# Codeshelf-0007_v03.net
KiCad netlist of a schematic drawn in EAGLE
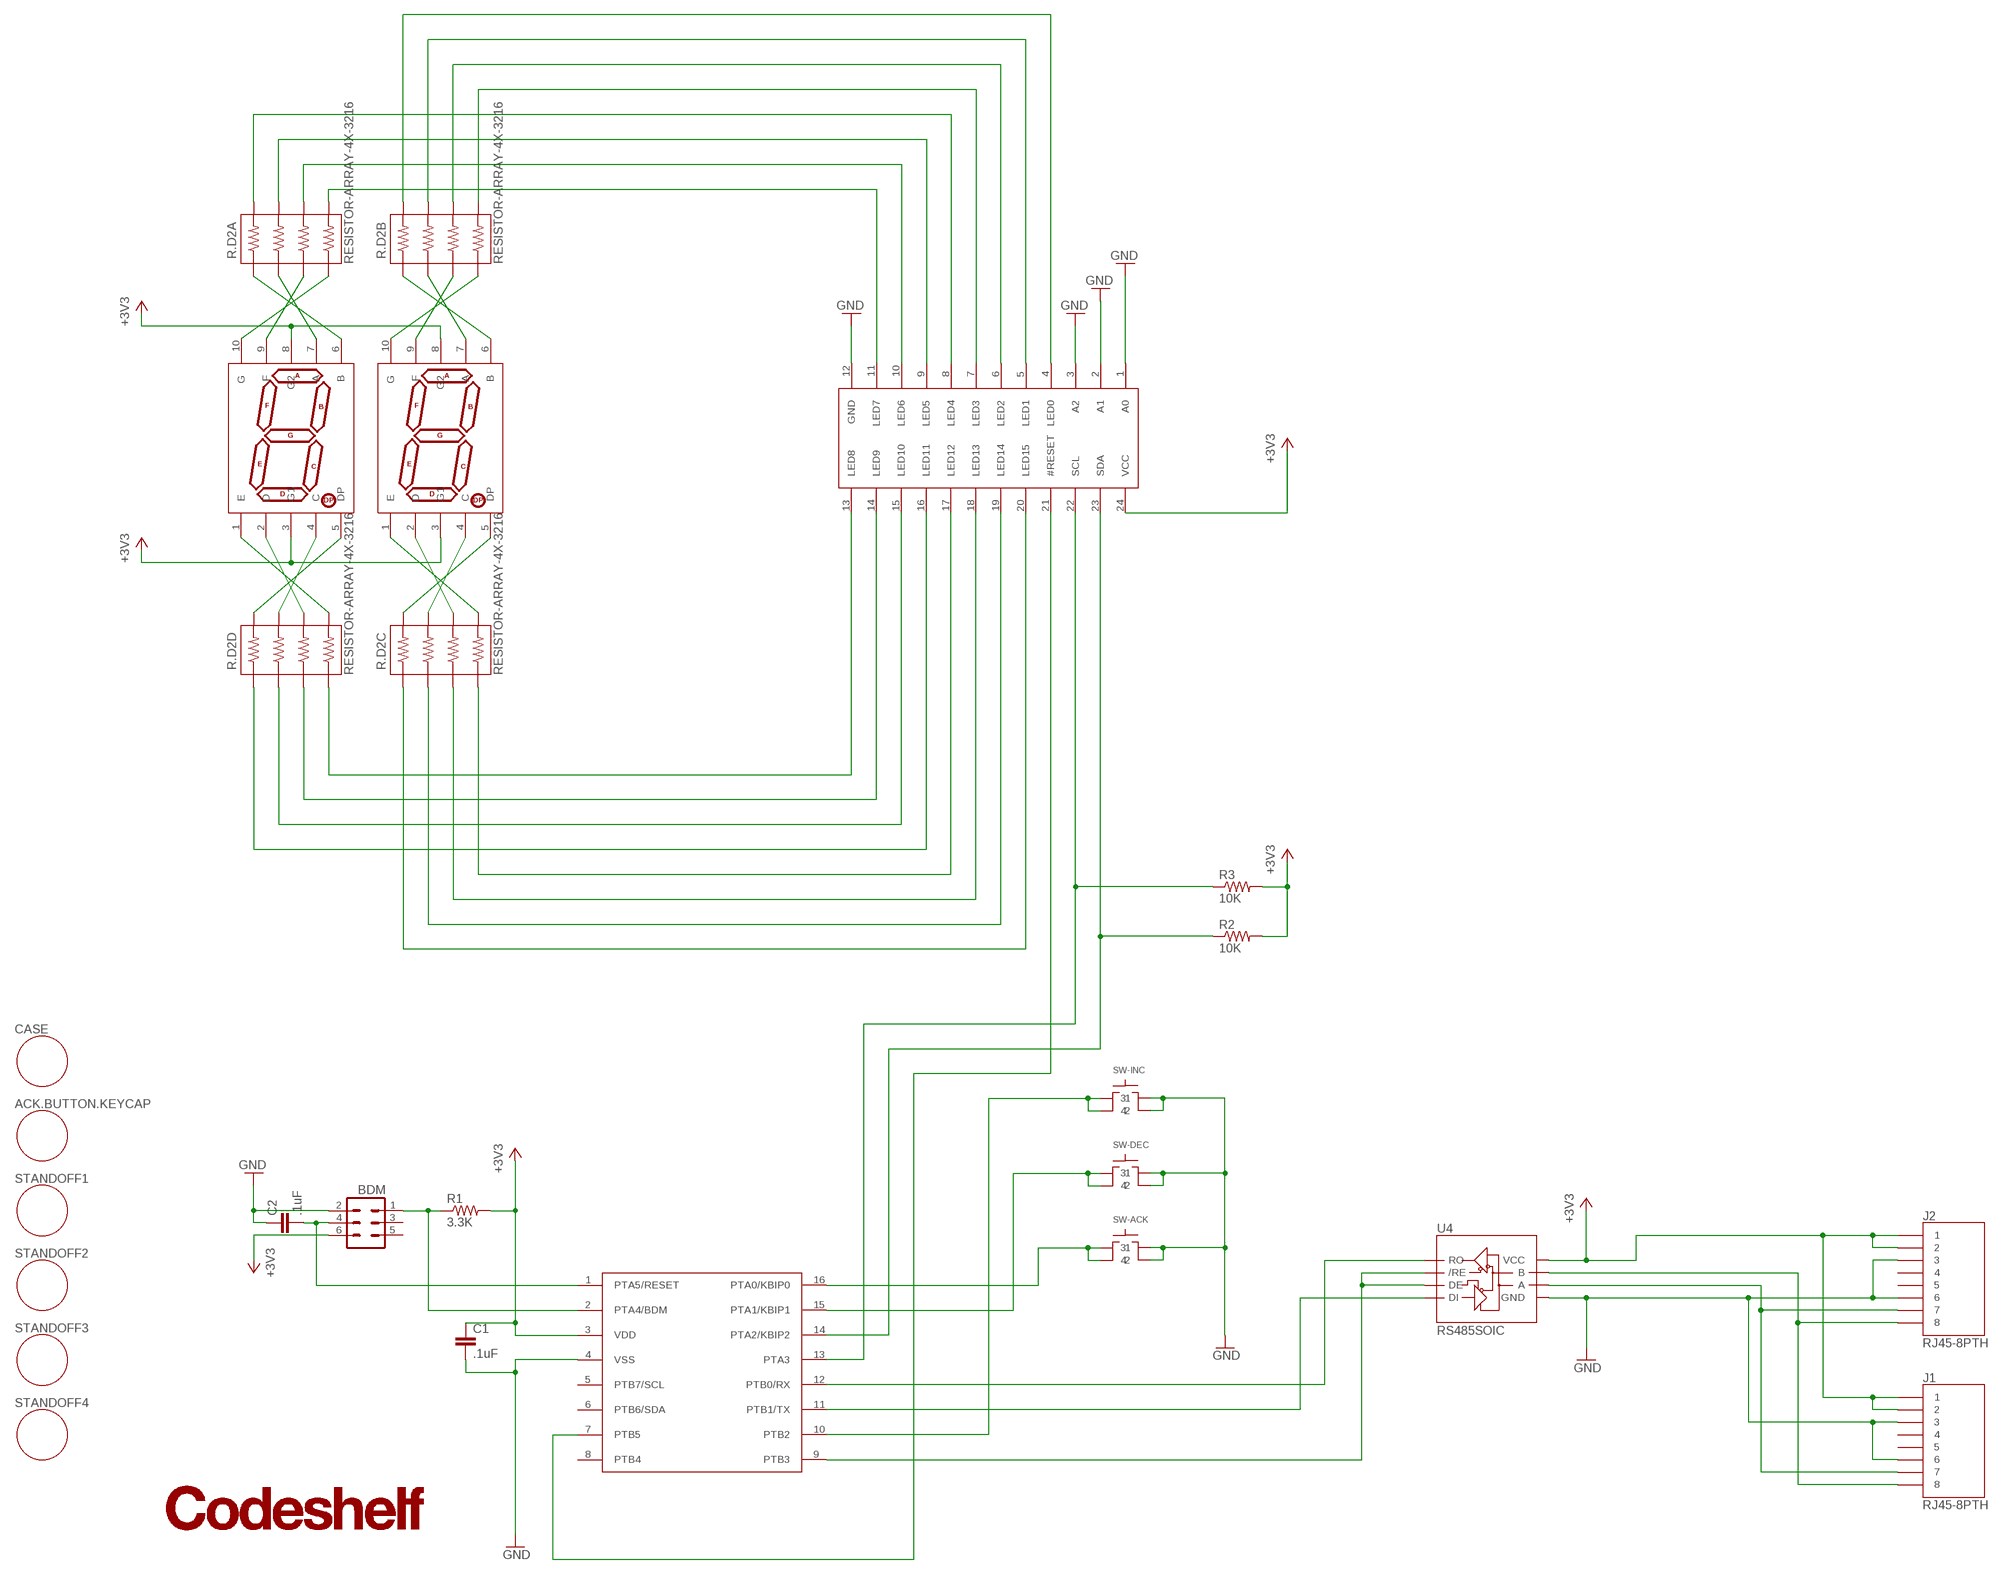
[diagram p0: schematic, sheet 1]

(export (version "E")
  (design (tool "Eeschema 10.0.6"))
  (components
    (comp (ref "ACK.BUTTON.KEYCAP")
      (value "EXTERNAL-COMPONENT")
      (footprint "eagle-import:EXTERNAL-COMPONENT")
      (libsource (lib "eagle-import") (part "EXTERNAL-COMPONENT"))
    )
    (comp (ref "BDM")
      (value "HEADER-3X2")
      (footprint "eagle-import:HEADER-3X2")
      (libsource (lib "eagle-import") (part "HEADER-3X2"))
    )
    (comp (ref "C1")
      (value ".1uF")
      (footprint "eagle-import:C0402")
      (libsource (lib "eagle-import") (part "RF-C0402"))
    )
    (comp (ref "C2")
      (value ".1uF")
      (footprint "eagle-import:C0402")
      (libsource (lib "eagle-import") (part "RF-C0402"))
    )
    (comp (ref "CASE")
      (value "EXTERNAL-COMPONENT")
      (footprint "eagle-import:EXTERNAL-COMPONENT")
      (libsource (lib "eagle-import") (part "EXTERNAL-COMPONENT"))
    )
    (comp (ref "J1")
      (value "RJ45-8PTH")
      (footprint "eagle-import:RJ45-8")
      (libsource (lib "eagle-import") (part "RJ45-8PTH"))
    )
    (comp (ref "J2")
      (value "RJ45-8PTH")
      (footprint "eagle-import:RJ45-8")
      (libsource (lib "eagle-import") (part "RJ45-8PTH"))
    )
    (comp (ref "LED1")
      (value "7SEGMENT-1DIGITSMD")
      (footprint "eagle-import:7SEGMENT-1DIG-.40-SMD")
      (libsource (lib "eagle-import") (part "7SEGMENT-1DIGITSMD"))
    )
    (comp (ref "LED2")
      (value "7SEGMENT-1DIGITSMD")
      (footprint "eagle-import:7SEGMENT-1DIG-.40-SMD")
      (libsource (lib "eagle-import") (part "7SEGMENT-1DIGITSMD"))
    )
    (comp (ref "LOGO")
      (value "CODESHELF-LOGO")
      (footprint "eagle-import:CODESHELF-LOGO")
      (libsource (lib "eagle-import") (part "CODESHELF-LOGO"))
    )
    (comp (ref "R.D2A")
      (value "RESISTOR-ARRAY-4X-3216")
      (footprint "eagle-import:3216-4X")
      (libsource (lib "eagle-import") (part "RESISTOR-ARRAY-4X-3216"))
    )
    (comp (ref "R.D2B")
      (value "RESISTOR-ARRAY-4X-3216")
      (footprint "eagle-import:3216-4X")
      (libsource (lib "eagle-import") (part "RESISTOR-ARRAY-4X-3216"))
    )
    (comp (ref "R.D2C")
      (value "RESISTOR-ARRAY-4X-3216")
      (footprint "eagle-import:3216-4X")
      (libsource (lib "eagle-import") (part "RESISTOR-ARRAY-4X-3216"))
    )
    (comp (ref "R.D2D")
      (value "RESISTOR-ARRAY-4X-3216")
      (footprint "eagle-import:3216-4X")
      (libsource (lib "eagle-import") (part "RESISTOR-ARRAY-4X-3216"))
    )
    (comp (ref "R1")
      (value "3.3K")
      (footprint "eagle-import:RF-R0402")
      (libsource (lib "eagle-import") (part "RF-R0402"))
    )
    (comp (ref "R2")
      (value "10K")
      (footprint "eagle-import:RF-R0402")
      (libsource (lib "eagle-import") (part "RF-R0402"))
    )
    (comp (ref "R3")
      (value "10K")
      (footprint "eagle-import:RF-R0402")
      (libsource (lib "eagle-import") (part "RF-R0402"))
    )
    (comp (ref "STANDOFF1")
      (value "EXTERNAL-COMPONENT")
      (footprint "eagle-import:EXTERNAL-COMPONENT")
      (libsource (lib "eagle-import") (part "EXTERNAL-COMPONENT"))
    )
    (comp (ref "STANDOFF2")
      (value "EXTERNAL-COMPONENT")
      (footprint "eagle-import:EXTERNAL-COMPONENT")
      (libsource (lib "eagle-import") (part "EXTERNAL-COMPONENT"))
    )
    (comp (ref "STANDOFF3")
      (value "EXTERNAL-COMPONENT")
      (footprint "eagle-import:EXTERNAL-COMPONENT")
      (libsource (lib "eagle-import") (part "EXTERNAL-COMPONENT"))
    )
    (comp (ref "STANDOFF4")
      (value "EXTERNAL-COMPONENT")
      (footprint "eagle-import:EXTERNAL-COMPONENT")
      (libsource (lib "eagle-import") (part "EXTERNAL-COMPONENT"))
    )
    (comp (ref "SW-ACK")
      (value "SWITCH-TACTILE-320.03E11")
      (footprint "eagle-import:SWITCH-TACTILE-320.03E11")
      (libsource (lib "eagle-import") (part "SWITCH-TACTILE-320.03E11"))
    )
    (comp (ref "SW-DEC")
      (value "SWITCH-TACTILE-FSM")
      (footprint "eagle-import:SWITCH-TACTILE-FSM")
      (libsource (lib "eagle-import") (part "SWITCH-TACTILE-FSM"))
    )
    (comp (ref "SW-INC")
      (value "SWITCH-TACTILE-FSM")
      (footprint "eagle-import:SWITCH-TACTILE-FSM")
      (libsource (lib "eagle-import") (part "SWITCH-TACTILE-FSM"))
    )
    (comp (ref "U2")
      (value "MC9S08QG-DT")
      (footprint "eagle-import:TSSOP16")
      (libsource (lib "eagle-import") (part "MC9S08QG-DT"))
    )
    (comp (ref "U3")
      (value "CAT9552")
      (footprint "eagle-import:TSSOP24")
      (libsource (lib "eagle-import") (part "CAT9552"))
    )
    (comp (ref "U4")
      (value "RS485SOIC")
      (footprint "eagle-import:SO08")
      (libsource (lib "eagle-import") (part "RS485SOIC"))
    )
  )
  (nets
    (net (code "1") (name "+3V3") (class "Default")
      (node (ref "BDM") (pin "6") (pinfunction "6_6") (pintype "passive"))
      (node (ref "C1") (pin "1") (pinfunction "1_1") (pintype "passive"))
      (node (ref "J1") (pin "1") (pinfunction "1_1") (pintype "bidirectional"))
      (node (ref "J1") (pin "2") (pinfunction "2_2") (pintype "bidirectional"))
      (node (ref "J2") (pin "1") (pinfunction "1_1") (pintype "bidirectional"))
      (node (ref "J2") (pin "2") (pinfunction "2_2") (pintype "bidirectional"))
      (node (ref "LED1") (pin "3") (pinfunction "G1_3") (pintype "bidirectional"))
      (node (ref "LED1") (pin "8") (pinfunction "G2_8") (pintype "bidirectional"))
      (node (ref "LED2") (pin "3") (pinfunction "G1_3") (pintype "bidirectional"))
      (node (ref "LED2") (pin "8") (pinfunction "G2_8") (pintype "bidirectional"))
      (node (ref "R1") (pin "2") (pinfunction "2_2") (pintype "passive"))
      (node (ref "R2") (pin "2") (pinfunction "2_2") (pintype "passive"))
      (node (ref "R3") (pin "2") (pinfunction "2_2") (pintype "passive"))
      (node (ref "U2") (pin "3") (pinfunction "VDD_3") (pintype "bidirectional"))
      (node (ref "U3") (pin "24") (pinfunction "VCC_24") (pintype "bidirectional"))
      (node (ref "U4") (pin "8") (pinfunction "VCC_8") (pintype "bidirectional"))
    )
    (net (code "2") (name "GND") (class "Default")
      (node (ref "BDM") (pin "2") (pinfunction "2_2") (pintype "passive"))
      (node (ref "C1") (pin "2") (pinfunction "2_2") (pintype "passive"))
      (node (ref "C2") (pin "1") (pinfunction "1_1") (pintype "passive"))
      (node (ref "J1") (pin "3") (pinfunction "3_3") (pintype "bidirectional"))
      (node (ref "J1") (pin "6") (pinfunction "6_6") (pintype "bidirectional"))
      (node (ref "J2") (pin "3") (pinfunction "3_3") (pintype "bidirectional"))
      (node (ref "J2") (pin "6") (pinfunction "6_6") (pintype "bidirectional"))
      (node (ref "SW-ACK") (pin "P$3") (pinfunction "3_P$3") (pintype "input"))
      (node (ref "SW-ACK") (pin "P$4") (pinfunction "4_P$4") (pintype "input"))
      (node (ref "SW-DEC") (pin "P$3") (pinfunction "3_P$3") (pintype "input"))
      (node (ref "SW-DEC") (pin "P$4") (pinfunction "4_P$4") (pintype "input"))
      (node (ref "SW-INC") (pin "P$3") (pinfunction "3_P$3") (pintype "input"))
      (node (ref "SW-INC") (pin "P$4") (pinfunction "4_P$4") (pintype "input"))
      (node (ref "U2") (pin "4") (pinfunction "VSS_4") (pintype "bidirectional"))
      (node (ref "U3") (pin "1") (pinfunction "A0_1") (pintype "bidirectional"))
      (node (ref "U3") (pin "12") (pinfunction "GND_12") (pintype "bidirectional"))
      (node (ref "U3") (pin "2") (pinfunction "A1_2") (pintype "bidirectional"))
      (node (ref "U3") (pin "3") (pinfunction "A2_3") (pintype "bidirectional"))
      (node (ref "U4") (pin "5") (pinfunction "GND_5") (pintype "bidirectional"))
    )
    (net (code "3") (name "Net-(LED1-A)") (class "Default")
      (node (ref "LED1") (pin "7") (pinfunction "A_7") (pintype "bidirectional"))
      (node (ref "R.D2B") (pin "2") (pinfunction "2A_2") (pintype "passive"))
    )
    (net (code "4") (name "Net-(LED1-B)") (class "Default")
      (node (ref "LED1") (pin "6") (pinfunction "B_6") (pintype "bidirectional"))
      (node (ref "R.D2B") (pin "1") (pinfunction "1A_1") (pintype "passive"))
    )
    (net (code "5") (name "Net-(LED1-C)") (class "Default")
      (node (ref "LED1") (pin "4") (pinfunction "C_4") (pintype "bidirectional"))
      (node (ref "R.D2C") (pin "7") (pinfunction "2B_7") (pintype "passive"))
    )
    (net (code "6") (name "Net-(LED1-D)") (class "Default")
      (node (ref "LED1") (pin "2") (pinfunction "D_2") (pintype "bidirectional"))
      (node (ref "R.D2C") (pin "6") (pinfunction "3B_6") (pintype "passive"))
    )
    (net (code "7") (name "Net-(LED1-DP)") (class "Default")
      (node (ref "LED1") (pin "5") (pinfunction "DP_5") (pintype "bidirectional"))
      (node (ref "R.D2C") (pin "8") (pinfunction "1B_8") (pintype "passive"))
    )
    (net (code "8") (name "Net-(LED1-E)") (class "Default")
      (node (ref "LED1") (pin "1") (pinfunction "E_1") (pintype "bidirectional"))
      (node (ref "R.D2C") (pin "5") (pinfunction "4B_5") (pintype "passive"))
    )
    (net (code "9") (name "Net-(LED1-F)") (class "Default")
      (node (ref "LED1") (pin "9") (pinfunction "F_9") (pintype "bidirectional"))
      (node (ref "R.D2B") (pin "3") (pinfunction "3A_3") (pintype "passive"))
    )
    (net (code "10") (name "Net-(LED1-G)") (class "Default")
      (node (ref "LED1") (pin "10") (pinfunction "G_10") (pintype "bidirectional"))
      (node (ref "R.D2B") (pin "4") (pinfunction "4A_4") (pintype "passive"))
    )
    (net (code "11") (name "Net-(LED2-A)") (class "Default")
      (node (ref "LED2") (pin "7") (pinfunction "A_7") (pintype "bidirectional"))
      (node (ref "R.D2A") (pin "2") (pinfunction "2A_2") (pintype "passive"))
    )
    (net (code "12") (name "Net-(LED2-B)") (class "Default")
      (node (ref "LED2") (pin "6") (pinfunction "B_6") (pintype "bidirectional"))
      (node (ref "R.D2A") (pin "1") (pinfunction "1A_1") (pintype "passive"))
    )
    (net (code "13") (name "Net-(LED2-C)") (class "Default")
      (node (ref "LED2") (pin "4") (pinfunction "C_4") (pintype "bidirectional"))
      (node (ref "R.D2D") (pin "7") (pinfunction "2B_7") (pintype "passive"))
    )
    (net (code "14") (name "Net-(LED2-D)") (class "Default")
      (node (ref "LED2") (pin "2") (pinfunction "D_2") (pintype "bidirectional"))
      (node (ref "R.D2D") (pin "6") (pinfunction "3B_6") (pintype "passive"))
    )
    (net (code "15") (name "Net-(LED2-DP)") (class "Default")
      (node (ref "LED2") (pin "5") (pinfunction "DP_5") (pintype "bidirectional"))
      (node (ref "R.D2D") (pin "8") (pinfunction "1B_8") (pintype "passive"))
    )
    (net (code "16") (name "Net-(LED2-E)") (class "Default")
      (node (ref "LED2") (pin "1") (pinfunction "E_1") (pintype "bidirectional"))
      (node (ref "R.D2D") (pin "5") (pinfunction "4B_5") (pintype "passive"))
    )
    (net (code "17") (name "Net-(LED2-F)") (class "Default")
      (node (ref "LED2") (pin "9") (pinfunction "F_9") (pintype "bidirectional"))
      (node (ref "R.D2A") (pin "3") (pinfunction "3A_3") (pintype "passive"))
    )
    (net (code "18") (name "Net-(LED2-G)") (class "Default")
      (node (ref "LED2") (pin "10") (pinfunction "G_10") (pintype "bidirectional"))
      (node (ref "R.D2A") (pin "4") (pinfunction "4A_4") (pintype "passive"))
    )
    (net (code "19") (name "Net-(R.D2A-1B)") (class "Default")
      (node (ref "R.D2A") (pin "8") (pinfunction "1B_8") (pintype "passive"))
      (node (ref "U3") (pin "8") (pinfunction "LED4_8") (pintype "bidirectional"))
    )
    (net (code "20") (name "Net-(R.D2A-2B)") (class "Default")
      (node (ref "R.D2A") (pin "7") (pinfunction "2B_7") (pintype "passive"))
      (node (ref "U3") (pin "9") (pinfunction "LED5_9") (pintype "bidirectional"))
    )
    (net (code "21") (name "Net-(R.D2A-3B)") (class "Default")
      (node (ref "R.D2A") (pin "6") (pinfunction "3B_6") (pintype "passive"))
      (node (ref "U3") (pin "10") (pinfunction "LED6_10") (pintype "bidirectional"))
    )
    (net (code "22") (name "Net-(R.D2A-4B)") (class "Default")
      (node (ref "R.D2A") (pin "5") (pinfunction "4B_5") (pintype "passive"))
      (node (ref "U3") (pin "11") (pinfunction "LED7_11") (pintype "bidirectional"))
    )
    (net (code "23") (name "Net-(R.D2B-1B)") (class "Default")
      (node (ref "R.D2B") (pin "8") (pinfunction "1B_8") (pintype "passive"))
      (node (ref "U3") (pin "4") (pinfunction "LED0_4") (pintype "bidirectional"))
    )
    (net (code "24") (name "Net-(R.D2B-2B)") (class "Default")
      (node (ref "R.D2B") (pin "7") (pinfunction "2B_7") (pintype "passive"))
      (node (ref "U3") (pin "5") (pinfunction "LED1_5") (pintype "bidirectional"))
    )
    (net (code "25") (name "Net-(R.D2B-3B)") (class "Default")
      (node (ref "R.D2B") (pin "6") (pinfunction "3B_6") (pintype "passive"))
      (node (ref "U3") (pin "6") (pinfunction "LED2_6") (pintype "bidirectional"))
    )
    (net (code "26") (name "Net-(R.D2B-4B)") (class "Default")
      (node (ref "R.D2B") (pin "5") (pinfunction "4B_5") (pintype "passive"))
      (node (ref "U3") (pin "7") (pinfunction "LED3_7") (pintype "bidirectional"))
    )
    (net (code "27") (name "Net-(R.D2C-1A)") (class "Default")
      (node (ref "R.D2C") (pin "1") (pinfunction "1A_1") (pintype "passive"))
      (node (ref "U3") (pin "20") (pinfunction "LED15_20") (pintype "bidirectional"))
    )
    (net (code "28") (name "Net-(R.D2C-2A)") (class "Default")
      (node (ref "R.D2C") (pin "2") (pinfunction "2A_2") (pintype "passive"))
      (node (ref "U3") (pin "19") (pinfunction "LED14_19") (pintype "bidirectional"))
    )
    (net (code "29") (name "Net-(R.D2C-3A)") (class "Default")
      (node (ref "R.D2C") (pin "3") (pinfunction "3A_3") (pintype "passive"))
      (node (ref "U3") (pin "18") (pinfunction "LED13_18") (pintype "bidirectional"))
    )
    (net (code "30") (name "Net-(R.D2C-4A)") (class "Default")
      (node (ref "R.D2C") (pin "4") (pinfunction "4A_4") (pintype "passive"))
      (node (ref "U3") (pin "17") (pinfunction "LED12_17") (pintype "bidirectional"))
    )
    (net (code "31") (name "Net-(R.D2D-1A)") (class "Default")
      (node (ref "R.D2D") (pin "1") (pinfunction "1A_1") (pintype "passive"))
      (node (ref "U3") (pin "16") (pinfunction "LED11_16") (pintype "bidirectional"))
    )
    (net (code "32") (name "Net-(R.D2D-2A)") (class "Default")
      (node (ref "R.D2D") (pin "2") (pinfunction "2A_2") (pintype "passive"))
      (node (ref "U3") (pin "15") (pinfunction "LED10_15") (pintype "bidirectional"))
    )
    (net (code "33") (name "Net-(R.D2D-3A)") (class "Default")
      (node (ref "R.D2D") (pin "3") (pinfunction "3A_3") (pintype "passive"))
      (node (ref "U3") (pin "14") (pinfunction "LED9_14") (pintype "bidirectional"))
    )
    (net (code "34") (name "Net-(R.D2D-4A)") (class "Default")
      (node (ref "R.D2D") (pin "4") (pinfunction "4A_4") (pintype "passive"))
      (node (ref "U3") (pin "13") (pinfunction "LED8_13") (pintype "bidirectional"))
    )
    (net (code "35") (name "Net-(SW-ACK-1)") (class "Default")
      (node (ref "SW-ACK") (pin "P$1") (pinfunction "1_P$1") (pintype "input"))
      (node (ref "SW-ACK") (pin "P$2") (pinfunction "2_P$2") (pintype "input"))
      (node (ref "U2") (pin "16") (pinfunction "PTA0/KBIP0_16") (pintype "bidirectional"))
    )
    (net (code "36") (name "Net-(SW-DEC-1)") (class "Default")
      (node (ref "SW-DEC") (pin "P$1") (pinfunction "1_P$1") (pintype "input"))
      (node (ref "SW-DEC") (pin "P$2") (pinfunction "2_P$2") (pintype "input"))
      (node (ref "U2") (pin "15") (pinfunction "PTA1/KBIP1_15") (pintype "bidirectional"))
    )
    (net (code "37") (name "Net-(SW-INC-1)") (class "Default")
      (node (ref "SW-INC") (pin "P$1") (pinfunction "1_P$1") (pintype "input"))
      (node (ref "SW-INC") (pin "P$2") (pinfunction "2_P$2") (pintype "input"))
      (node (ref "U2") (pin "10") (pinfunction "PTB2_10") (pintype "bidirectional"))
    )
    (net (code "38") (name "Net-(U2-PTA2{slash}KBIP2)") (class "Default")
      (node (ref "R2") (pin "1") (pinfunction "1_1") (pintype "passive"))
      (node (ref "U2") (pin "14") (pinfunction "PTA2/KBIP2_14") (pintype "bidirectional"))
      (node (ref "U3") (pin "23") (pinfunction "SDA_23") (pintype "bidirectional"))
    )
    (net (code "39") (name "Net-(U2-PTA3)") (class "Default")
      (node (ref "R3") (pin "1") (pinfunction "1_1") (pintype "passive"))
      (node (ref "U2") (pin "13") (pinfunction "PTA3_13") (pintype "bidirectional"))
      (node (ref "U3") (pin "22") (pinfunction "SCL_22") (pintype "bidirectional"))
    )
    (net (code "40") (name "Net-(U2-PTA4{slash}BDM)") (class "Default")
      (node (ref "BDM") (pin "1") (pinfunction "1_1") (pintype "passive"))
      (node (ref "R1") (pin "1") (pinfunction "1_1") (pintype "passive"))
      (node (ref "U2") (pin "2") (pinfunction "PTA4/BDM_2") (pintype "bidirectional"))
    )
    (net (code "41") (name "Net-(U2-PTA5{slash}RESET)") (class "Default")
      (node (ref "BDM") (pin "4") (pinfunction "4_4") (pintype "passive"))
      (node (ref "C2") (pin "2") (pinfunction "2_2") (pintype "passive"))
      (node (ref "U2") (pin "1") (pinfunction "PTA5/RESET_1") (pintype "bidirectional"))
    )
    (net (code "42") (name "Net-(U2-PTB0{slash}RX)") (class "Default")
      (node (ref "U2") (pin "12") (pinfunction "PTB0/RX_12") (pintype "bidirectional"))
      (node (ref "U4") (pin "1") (pinfunction "RO_1") (pintype "bidirectional"))
    )
    (net (code "43") (name "Net-(U2-PTB1{slash}TX)") (class "Default")
      (node (ref "U2") (pin "11") (pinfunction "PTB1/TX_11") (pintype "bidirectional"))
      (node (ref "U4") (pin "4") (pinfunction "DI_4") (pintype "bidirectional"))
    )
    (net (code "44") (name "Net-(U2-PTB3)") (class "Default")
      (node (ref "U2") (pin "9") (pinfunction "PTB3_9") (pintype "bidirectional"))
      (node (ref "U4") (pin "2") (pinfunction "/RE_2") (pintype "bidirectional"))
      (node (ref "U4") (pin "3") (pinfunction "DE_3") (pintype "bidirectional"))
    )
    (net (code "45") (name "Net-(U2-PTB5)") (class "Default")
      (node (ref "U2") (pin "7") (pinfunction "PTB5_7") (pintype "bidirectional"))
      (node (ref "U3") (pin "21") (pinfunction "#RESET_21") (pintype "bidirectional"))
    )
    (net (code "46") (name "Net-(U4-A)") (class "Default")
      (node (ref "J1") (pin "7") (pinfunction "7_7") (pintype "bidirectional"))
      (node (ref "J2") (pin "7") (pinfunction "7_7") (pintype "bidirectional"))
      (node (ref "U4") (pin "6") (pinfunction "A_6") (pintype "bidirectional"))
    )
    (net (code "47") (name "Net-(U4-B)") (class "Default")
      (node (ref "J1") (pin "8") (pinfunction "8_8") (pintype "bidirectional"))
      (node (ref "J2") (pin "8") (pinfunction "8_8") (pintype "bidirectional"))
      (node (ref "U4") (pin "7") (pinfunction "B_7") (pintype "bidirectional"))
    )
    (net (code "48") (name "unconnected-(BDM-Pad3)") (class "Default")
      (node (ref "BDM") (pin "3") (pinfunction "3_3") (pintype "passive"))
    )
    (net (code "49") (name "unconnected-(BDM-Pad5)") (class "Default")
      (node (ref "BDM") (pin "5") (pinfunction "5_5") (pintype "passive"))
    )
    (net (code "50") (name "unconnected-(J1-Pad4)") (class "Default")
      (node (ref "J1") (pin "4") (pinfunction "4_4") (pintype "bidirectional"))
    )
    (net (code "51") (name "unconnected-(J1-Pad5)") (class "Default")
      (node (ref "J1") (pin "5") (pinfunction "5_5") (pintype "bidirectional"))
    )
    (net (code "52") (name "unconnected-(J2-Pad4)") (class "Default")
      (node (ref "J2") (pin "4") (pinfunction "4_4") (pintype "bidirectional"))
    )
    (net (code "53") (name "unconnected-(J2-Pad5)") (class "Default")
      (node (ref "J2") (pin "5") (pinfunction "5_5") (pintype "bidirectional"))
    )
    (net (code "54") (name "unconnected-(U2-PTB4-Pad8)") (class "Default")
      (node (ref "U2") (pin "8") (pinfunction "PTB4_8") (pintype "bidirectional"))
    )
    (net (code "55") (name "unconnected-(U2-PTB6{slash}SDA-Pad6)") (class "Default")
      (node (ref "U2") (pin "6") (pinfunction "PTB6/SDA_6") (pintype "bidirectional"))
    )
    (net (code "56") (name "unconnected-(U2-PTB7{slash}SCL-Pad5)") (class "Default")
      (node (ref "U2") (pin "5") (pinfunction "PTB7/SCL_5") (pintype "bidirectional"))
    )
  )
)
